# 6-E2p_RTC.net
KiCad netlist of a schematic drawn in Altium Designer
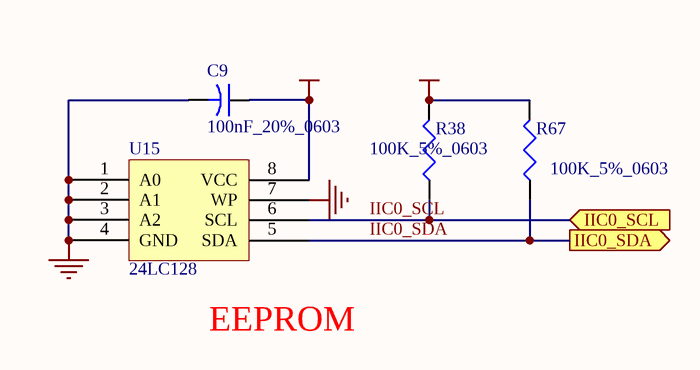
[diagram p0: 6-E2p&RTC.SchDoc]

(export (version "E")
  (design (tool "Eeschema 10.0.6"))
  (components
    (comp (ref "C9")
      (value "100nF_20%_0603")
      (footprint "C1608-0603")
      (description "Capacitor")
      (fields (field (name "PUBLISHER") "Altium Limited"))
      (libsource (lib "Miscellaneous Devices") (part "Cap2"))
    )
    (comp (ref "R38")
      (value "100K_5%_0603")
      (footprint "C1608-0603")
      (description "Resistor")
      (fields (field (name "PUBLISHER") "Altium Limited"))
      (libsource (lib "Miscellaneous Devices") (part "Res3"))
    )
    (comp (ref "R67")
      (value "100K_5%_0603")
      (footprint "C1608-0603")
      (description "Resistor")
      (fields (field (name "PUBLISHER") "Altium Limited"))
      (libsource (lib "Miscellaneous Devices") (part "Res3"))
    )
    (comp (ref "U15")
      (value "24LC128")
      (footprint "8s1")
      (description "IC")
      (libsource (lib "24LC02") (part "24LC02"))
    )
  )
  (nets
    (net (code "1") (name "/IIC0_SCL") (class "Default")
      (node (ref "R38") (pin "1") (pinfunction "1_1") (pintype "passive"))
      (node (ref "U15") (pin "6") (pinfunction "SCL_6") (pintype "passive"))
    )
    (net (code "2") (name "/IIC0_SDA") (class "Default")
      (node (ref "R67") (pin "1") (pinfunction "1_1") (pintype "passive"))
      (node (ref "U15") (pin "5") (pinfunction "SDA_5") (pintype "passive"))
    )
    (net (code "3") (name "GND") (class "Default")
      (node (ref "C9") (pin "2") (pinfunction "2_2") (pintype "passive"))
      (node (ref "U15") (pin "1") (pinfunction "A0_1") (pintype "passive"))
      (node (ref "U15") (pin "2") (pinfunction "A1_2") (pintype "passive"))
      (node (ref "U15") (pin "3") (pinfunction "A2_3") (pintype "passive"))
      (node (ref "U15") (pin "4") (pinfunction "GND_4") (pintype "passive"))
      (node (ref "U15") (pin "7") (pinfunction "WP_7") (pintype "passive"))
    )
    (net (code "4") (name "VCC_2V8") (class "Default")
      (node (ref "C9") (pin "1") (pinfunction "1_1") (pintype "passive"))
      (node (ref "R38") (pin "2") (pinfunction "2_2") (pintype "passive"))
      (node (ref "R67") (pin "2") (pinfunction "2_2") (pintype "passive"))
      (node (ref "U15") (pin "8") (pinfunction "VCC_8") (pintype "passive"))
    )
  )
)
